# 05_-_ENERGY_STORAGE_AND_PROTECTION.net
KiCad netlist of a schematic drawn in Altium Designer
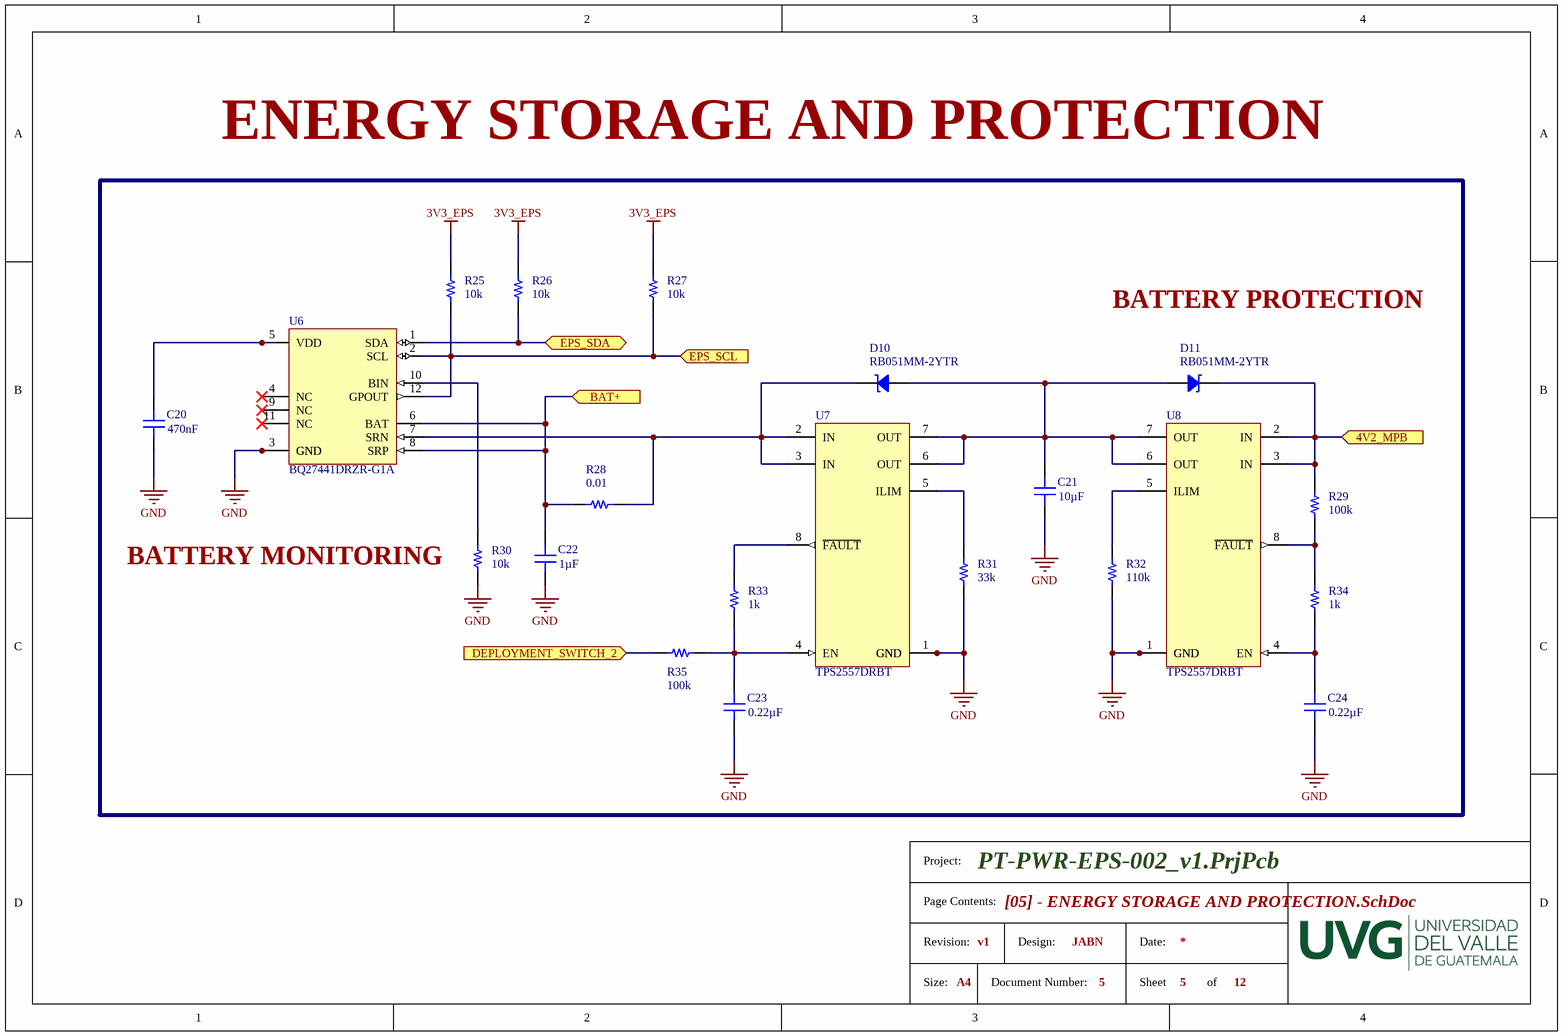
[diagram p0: [05] - ENERGY STORAGE AND PROTECTION.SchDoc]

(export (version "E")
  (design (tool "Eeschema 10.0.6"))
  (components
    (comp (ref "C20")
      (value "CL10B474KA8NFNC")
      (footprint "RES 0603/1608")
      (description "CAP CER 0.47UF 25V X7R 0603")
      (fields
        (field (name "MANUFACTURER") "Samsung")
        (field (name "CAPACITANCE") "470nF")
        (field (name "TOLERANCE") "10%")
      )
      (libsource (lib "UVG") (part "CL10B474KA8NFNC"))
    )
    (comp (ref "C21")
      (value "CL10A106MQ8NNNC")
      (footprint "CAP 0603/1608")
      (description "CAP CER 10UF 6.3V X5R 0603")
      (fields
        (field (name "MANUFACTURER") "Samsung")
        (field (name "CAPACITANCE") "10µF")
        (field (name "TOLERANCE") "20%")
      )
      (libsource (lib "UVG") (part "CL10A106MQ8NNNC"))
    )
    (comp (ref "C22")
      (value "CL10A105KP8NNNC")
      (footprint "CAP 0603/1608")
      (description "CAP CER 1UF 10V X5R 0603")
      (fields
        (field (name "MANUFACTURER") "Samsung")
        (field (name "TOLERANCE") "10%")
        (field (name "CAPACITANCE") "1µF")
      )
      (libsource (lib "UVG") (part "CL10A105KP8NNNC"))
    )
    (comp (ref "C23")
      (value "EMK107B7224KA-T")
      (footprint "CAP 0603/1608")
      (description "CAP CER 0.22UF 16V X7R 0603")
      (libsource (lib "UVG") (part "EMK107B7224KA-T"))
    )
    (comp (ref "C24")
      (value "EMK107B7224KA-T")
      (footprint "CAP 0603/1608")
      (description "CAP CER 0.22UF 16V X7R 0603")
      (libsource (lib "UVG") (part "EMK107B7224KA-T"))
    )
    (comp (ref "D10")
      (value "RB051MM-2YTR")
      (footprint "SOD123F")
      (description "DIODE SCHOTTKY 20V 3A PMDU")
      (fields (field (name "MANUFACTURER") "Rohm"))
      (libsource (lib "UVG") (part "RB051MM-2YTR"))
    )
    (comp (ref "D11")
      (value "RB051MM-2YTR")
      (footprint "SOD123F")
      (description "DIODE SCHOTTKY 20V 3A PMDU")
      (fields (field (name "MANUFACTURER") "Rohm"))
      (libsource (lib "UVG") (part "RB051MM-2YTR"))
    )
    (comp (ref "R25")
      (value "RNCP0603FTD10K0")
      (footprint "RES 0603/1608")
      (description "RES SMD 10K OHM 1% 1/8W 0603")
      (fields
        (field (name "MANUFACTURER") "Stackpole Electronics")
        (field (name "RESISTANCE") "10k")
        (field (name "TOLERANCE") "1%")
      )
      (libsource (lib "UVG") (part "RNCP0603FTD10K0"))
    )
    (comp (ref "R26")
      (value "RNCP0603FTD10K0")
      (footprint "RES 0603/1608")
      (description "RES SMD 10K OHM 1% 1/8W 0603")
      (fields
        (field (name "MANUFACTURER") "Stackpole Electronics")
        (field (name "RESISTANCE") "10k")
        (field (name "TOLERANCE") "1%")
      )
      (libsource (lib "UVG") (part "RNCP0603FTD10K0"))
    )
    (comp (ref "R27")
      (value "RNCP0603FTD10K0")
      (footprint "RES 0603/1608")
      (description "RES SMD 10K OHM 1% 1/8W 0603")
      (fields
        (field (name "MANUFACTURER") "Stackpole Electronics")
        (field (name "RESISTANCE") "10k")
        (field (name "TOLERANCE") "1%")
      )
      (libsource (lib "UVG") (part "RNCP0603FTD10K0"))
    )
    (comp (ref "R28")
      (value "CSRN2010FK10L0")
      (footprint "STACKPOLE CSR2010")
      (description "RES 0.01 OHM 1% 1W 2010")
      (fields
        (field (name "MANUFACTURER") "Stackpole Electronics")
        (field (name "RESISTANCE") "0.01")
        (field (name "TOLERANCE") "1%")
      )
      (libsource (lib "UVG") (part "CSRN2010FK10L0"))
    )
    (comp (ref "R29")
      (value "CR0603-JW-104ELF")
      (footprint "RES 0603/1608")
      (description "RES SMD 100K OHM 5% 1/10W 0603")
      (fields
        (field (name "MANUFACTURER") "Bourns")
        (field (name "RESISTANCE") "100k")
        (field (name "TOLERANCE") "5%")
      )
      (libsource (lib "UVG") (part "CR0603-JW-104ELF"))
    )
    (comp (ref "R30")
      (value "RNCP0603FTD10K0")
      (footprint "RES 0603/1608")
      (description "RES SMD 10K OHM 1% 1/8W 0603")
      (fields
        (field (name "MANUFACTURER") "Stackpole Electronics")
        (field (name "RESISTANCE") "10k")
        (field (name "TOLERANCE") "1%")
      )
      (libsource (lib "UVG") (part "RNCP0603FTD10K0"))
    )
    (comp (ref "R31")
      (value "CRGCQ0603F33K")
      (footprint "RES 0603/1608")
      (description "RES SMD 33K OHM 1% 1/10W 0603")
      (fields (field (name "MANUFACTURER") "TE Connectivity"))
      (libsource (lib "UVG") (part "CRGCQ0603F33K"))
    )
    (comp (ref "R32")
      (value "RC0603FR-07110KL")
      (footprint "RES 0603/1608")
      (description "RES SMD 110K OHM 1% 1/10W 0603")
      (fields
        (field (name "MANUFACTURER") "Yageo")
        (field (name "TOLERANCE") "1%")
        (field (name "RESISTANCE") "110k")
      )
      (libsource (lib "UVG") (part "RC0603FR-07110KL"))
    )
    (comp (ref "R33")
      (value "ESR03EZPJ102")
      (footprint "RES 0603/1608")
      (description "RES SMD 1K OHM 5% 1/4W 0603")
      (fields
        (field (name "MANUFACTURER") "Rohm")
        (field (name "RESISTANCE") "1k")
        (field (name "TOLERANCE") "5%")
      )
      (libsource (lib "UVG") (part "ESR03EZPJ102"))
    )
    (comp (ref "R34")
      (value "ESR03EZPJ102")
      (footprint "RES 0603/1608")
      (description "RES SMD 1K OHM 5% 1/4W 0603")
      (fields
        (field (name "MANUFACTURER") "Rohm")
        (field (name "RESISTANCE") "1k")
        (field (name "TOLERANCE") "5%")
      )
      (libsource (lib "UVG") (part "ESR03EZPJ102"))
    )
    (comp (ref "R35")
      (value "CR0603-JW-104ELF")
      (footprint "RES 0603/1608")
      (description "RES SMD 100K OHM 5% 1/10W 0603")
      (fields
        (field (name "MANUFACTURER") "Bourns")
        (field (name "RESISTANCE") "100k")
        (field (name "TOLERANCE") "5%")
      )
      (libsource (lib "UVG") (part "CR0603-JW-104ELF"))
    )
    (comp (ref "U6")
      (value "BQ27441DRZR-G1A")
      (footprint "12-VFDFN")
      (description "IC BATT FUEL GAUGE LI-ION 12SON")
      (fields (field (name "MANUFACTURER") "Texas Instruments"))
      (libsource (lib "UVG") (part "BQ27441DRZR-G1A"))
    )
    (comp (ref "U7")
      (value "TPS2557DRBT")
      (footprint "8-VDFN")
      (description "IC PWR DIST SWITCH ADJ 8SON")
      (fields (field (name "MANUFACTURER") "Texas Instruments") (field (name "VOLTAGE") "6.5V"))
      (libsource (lib "") (part "TPS2557DRBT_1"))
    )
    (comp (ref "U8")
      (value "TPS2557DRBT")
      (footprint "8-VDFN")
      (description "IC PWR DIST SWITCH ADJ 8SON")
      (fields (field (name "MANUFACTURER") "Texas Instruments") (field (name "VOLTAGE") "6.5V"))
      (libsource (lib "UVG") (part "TPS2557DRBT"))
    )
  )
  (nets
    (net (code "1") (name "/4V2_MPB") (class "Default")
      (node (ref "D11") (pin "2") (pinfunction "2_2") (pintype "passive"))
      (node (ref "R29") (pin "2") (pinfunction "2_2") (pintype "passive"))
      (node (ref "U8") (pin "2") (pinfunction "IN_2") (pintype "power_in"))
      (node (ref "U8") (pin "3") (pinfunction "IN_3") (pintype "power_in"))
    )
    (net (code "2") (name "/BAT+") (class "Default")
      (node (ref "C22") (pin "2") (pinfunction "2_2") (pintype "passive"))
      (node (ref "R28") (pin "2") (pinfunction "2_2") (pintype "passive"))
      (node (ref "U6") (pin "6") (pinfunction "BAT_6") (pintype "power_in"))
      (node (ref "U6") (pin "8") (pinfunction "SRP_8") (pintype "input"))
    )
    (net (code "3") (name "/DEPLOYMENT_SWITCH_2") (class "Default")
      (node (ref "R35") (pin "1") (pinfunction "1_1") (pintype "passive"))
    )
    (net (code "4") (name "/EPS_SCL") (class "Default")
      (node (ref "R25") (pin "1") (pinfunction "1_1") (pintype "passive"))
      (node (ref "R27") (pin "1") (pinfunction "1_1") (pintype "passive"))
      (node (ref "U6") (pin "12") (pinfunction "GPOUT_12") (pintype "output"))
      (node (ref "U6") (pin "2") (pinfunction "SCL_2") (pintype "bidirectional"))
    )
    (net (code "5") (name "/EPS_SDA") (class "Default")
      (node (ref "R26") (pin "1") (pinfunction "1_1") (pintype "passive"))
      (node (ref "U6") (pin "1") (pinfunction "SDA_1") (pintype "bidirectional"))
    )
    (net (code "6") (name "3V3_EPS") (class "Default")
      (node (ref "R25") (pin "2") (pinfunction "2_2") (pintype "passive"))
      (node (ref "R26") (pin "2") (pinfunction "2_2") (pintype "passive"))
      (node (ref "R27") (pin "2") (pinfunction "2_2") (pintype "passive"))
    )
    (net (code "7") (name "GND") (class "Default")
      (node (ref "C20") (pin "1") (pinfunction "1_1") (pintype "passive"))
      (node (ref "C21") (pin "1") (pinfunction "1_1") (pintype "passive"))
      (node (ref "C22") (pin "1") (pinfunction "1_1") (pintype "passive"))
      (node (ref "C23") (pin "1") (pinfunction "1_1") (pintype "passive"))
      (node (ref "C24") (pin "1") (pinfunction "1_1") (pintype "passive"))
      (node (ref "R30") (pin "1") (pinfunction "1_1") (pintype "passive"))
      (node (ref "R31") (pin "1") (pinfunction "1_1") (pintype "passive"))
      (node (ref "R32") (pin "1") (pinfunction "1_1") (pintype "passive"))
      (node (ref "U6") (pin "13") (pinfunction "GND_13") (pintype "power_in"))
      (node (ref "U6") (pin "3") (pinfunction "GND_3") (pintype "power_in"))
      (node (ref "U7") (pin "1") (pinfunction "GND_1") (pintype "power_in"))
      (node (ref "U7") (pin "9") (pinfunction "GND_9") (pintype "power_in"))
      (node (ref "U8") (pin "1") (pinfunction "GND_1") (pintype "power_in"))
      (node (ref "U8") (pin "9") (pinfunction "GND_9") (pintype "power_in"))
    )
    (net (code "8") (name "Net-(C21-Pad2)") (class "Default")
      (node (ref "C21") (pin "2") (pinfunction "2_2") (pintype "passive"))
      (node (ref "D10") (pin "1") (pinfunction "1_1") (pintype "passive"))
      (node (ref "D11") (pin "1") (pinfunction "1_1") (pintype "passive"))
      (node (ref "U7") (pin "6") (pinfunction "OUT_6") (pintype "power_in"))
      (node (ref "U7") (pin "7") (pinfunction "OUT_7") (pintype "power_in"))
      (node (ref "U8") (pin "6") (pinfunction "OUT_6") (pintype "power_in"))
      (node (ref "U8") (pin "7") (pinfunction "OUT_7") (pintype "power_in"))
    )
    (net (code "9") (name "Net-(U6-BIN)") (class "Default")
      (node (ref "R30") (pin "2") (pinfunction "2_2") (pintype "passive"))
      (node (ref "U6") (pin "10") (pinfunction "BIN_10") (pintype "input"))
    )
    (net (code "10") (name "Net-(U6-SRN)") (class "Default")
      (node (ref "D10") (pin "2") (pinfunction "2_2") (pintype "passive"))
      (node (ref "R28") (pin "1") (pinfunction "1_1") (pintype "passive"))
      (node (ref "U6") (pin "7") (pinfunction "SRN_7") (pintype "input"))
      (node (ref "U7") (pin "2") (pinfunction "IN_2") (pintype "power_in"))
      (node (ref "U7") (pin "3") (pinfunction "IN_3") (pintype "power_in"))
    )
    (net (code "11") (name "Net-(U6-VDD)") (class "Default")
      (node (ref "C20") (pin "2") (pinfunction "2_2") (pintype "passive"))
      (node (ref "U6") (pin "5") (pinfunction "VDD_5") (pintype "power_in"))
    )
    (net (code "12") (name "Net-(U7-EN)") (class "Default")
      (node (ref "C23") (pin "2") (pinfunction "2_2") (pintype "passive"))
      (node (ref "R33") (pin "1") (pinfunction "1_1") (pintype "passive"))
      (node (ref "R35") (pin "2") (pinfunction "2_2") (pintype "passive"))
      (node (ref "U7") (pin "4") (pinfunction "EN_4") (pintype "input"))
    )
    (net (code "13") (name "Net-(U7-ILIM)") (class "Default")
      (node (ref "R31") (pin "2") (pinfunction "2_2") (pintype "passive"))
      (node (ref "U7") (pin "5") (pinfunction "ILIM_5") (pintype "passive"))
    )
    (net (code "14") (name "Net-(U7-~{FAULT})") (class "Default")
      (node (ref "R33") (pin "2") (pinfunction "2_2") (pintype "passive"))
      (node (ref "U7") (pin "8") (pinfunction "~{FAULT}_8") (pintype "output"))
    )
    (net (code "15") (name "Net-(U8-EN)") (class "Default")
      (node (ref "C24") (pin "2") (pinfunction "2_2") (pintype "passive"))
      (node (ref "R34") (pin "1") (pinfunction "1_1") (pintype "passive"))
      (node (ref "U8") (pin "4") (pinfunction "EN_4") (pintype "input"))
    )
    (net (code "16") (name "Net-(U8-ILIM)") (class "Default")
      (node (ref "R32") (pin "2") (pinfunction "2_2") (pintype "passive"))
      (node (ref "U8") (pin "5") (pinfunction "ILIM_5") (pintype "passive"))
    )
    (net (code "17") (name "Net-(U8-~{FAULT})") (class "Default")
      (node (ref "R29") (pin "1") (pinfunction "1_1") (pintype "passive"))
      (node (ref "R34") (pin "2") (pinfunction "2_2") (pintype "passive"))
      (node (ref "U8") (pin "8") (pinfunction "~{FAULT}_8") (pintype "output"))
    )
    (net (code "18") (name "unconnected-(U6-NC-Pad4)") (class "Default")
      (node (ref "U6") (pin "4") (pinfunction "NC_4") (pintype "passive+no_connect"))
    )
    (net (code "19") (name "unconnected-(U6-NC-Pad9)") (class "Default")
      (node (ref "U6") (pin "9") (pinfunction "NC_9") (pintype "passive+no_connect"))
    )
    (net (code "20") (name "unconnected-(U6-NC-Pad11)") (class "Default")
      (node (ref "U6") (pin "11") (pinfunction "NC_11") (pintype "passive+no_connect"))
    )
  )
)
